# P06_BoosterPack_Headers.net
KiCad netlist of a schematic drawn in Altium Designer
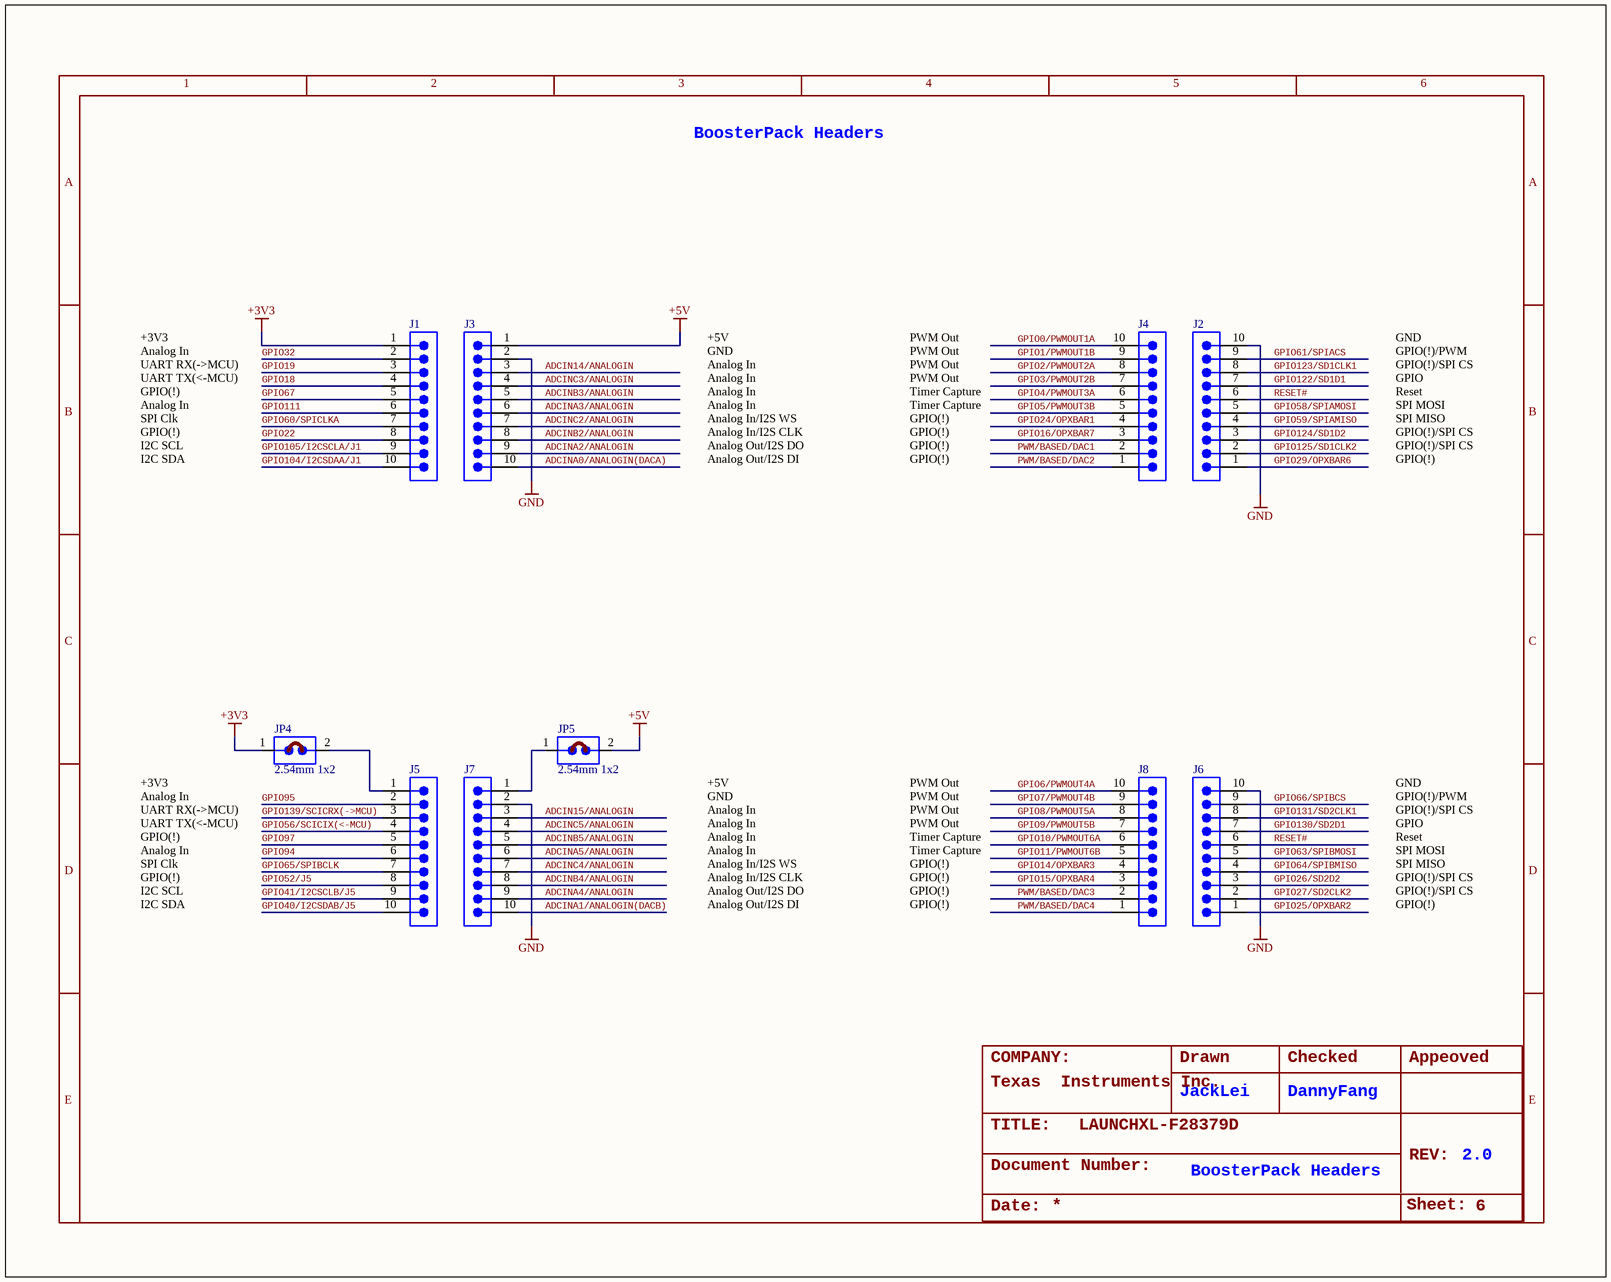
[diagram p0: P06_BoosterPack Headers.SchDoc]

(export (version "E")
  (design (tool "Eeschema 10.0.6"))
  (components
    (comp (ref "J1")
      (value "FH2543-10GT10")
      (footprint "SOKV2W64P254_1X10_2590X250X850P")
      (description "Connector,Pin Socket,Straight,Female,1x10Pin,2.54MM pitch,8.5,3.2,Gold Flash 1u,black,DIP")
      (fields (field (name "MANUFACTURER") "MTCONN"))
      (libsource (lib "") (part "SIP10_1"))
    )
    (comp (ref "J2")
      (value "FH2543-10GT10")
      (footprint "SOKV2W64P254_1X10_2590X250X850P")
      (description "Connector,Pin Socket,Straight,Female,1x10Pin,2.54MM pitch,8.5,3.2,Gold Flash 1u,black,DIP")
      (fields (field (name "MANUFACTURER") "MTCONN"))
      (libsource (lib "") (part "SIP10_3"))
    )
    (comp (ref "J3")
      (value "FH2543-10GT10")
      (footprint "SOKV2W64P254_1X10_2590X250X850P")
      (description "Connector,Pin Socket,Straight,Female,1x10Pin,2.54MM pitch,8.5,3.2,Gold Flash 1u,black,DIP")
      (fields (field (name "MANUFACTURER") "MTCONN"))
      (libsource (lib "Embest") (part "SIP10"))
    )
    (comp (ref "J4")
      (value "FH2543-10GT10")
      (footprint "SOKV2W64P254_1X10_2590X250X850P")
      (description "Connector,Pin Socket,Straight,Female,1x10Pin,2.54MM pitch,8.5,3.2,Gold Flash 1u,black,DIP")
      (fields (field (name "MANUFACTURER") "MTCONN"))
      (libsource (lib "") (part "SIP10_2"))
    )
    (comp (ref "J5")
      (value "FH2543-10GT10")
      (footprint "SOKV2W64P254_1X10_2590X250X850P")
      (description "Connector,Pin Socket,Straight,Female,1x10Pin,2.54MM pitch,8.5,3.2,Gold Flash 1u,black,DIP")
      (fields (field (name "MANUFACTURER") "MTCONN"))
      (libsource (lib "") (part "SIP10_1"))
    )
    (comp (ref "J6")
      (value "FH2543-10GT10")
      (footprint "SOKV2W64P254_1X10_2590X250X850P")
      (description "Connector,Pin Socket,Straight,Female,1x10Pin,2.54MM pitch,8.5,3.2,Gold Flash 1u,black,DIP")
      (fields (field (name "MANUFACTURER") "MTCONN"))
      (libsource (lib "") (part "SIP10_3"))
    )
    (comp (ref "J7")
      (value "FH2543-10GT10")
      (footprint "SOKV2W64P254_1X10_2590X250X850P")
      (description "Connector,Pin Socket,Straight,Female,1x10Pin,2.54MM pitch,8.5,3.2,Gold Flash 1u,black,DIP")
      (fields (field (name "MANUFACTURER") "MTCONN"))
      (libsource (lib "Embest") (part "SIP10"))
    )
    (comp (ref "J8")
      (value "FH2543-10GT10")
      (footprint "SOKV2W64P254_1X10_2590X250X850P")
      (description "Connector,Pin Socket,Straight,Female,1x10Pin,2.54MM pitch,8.5,3.2,Gold Flash 1u,black,DIP")
      (fields (field (name "MANUFACTURER") "MTCONN"))
      (libsource (lib "") (part "SIP10_2"))
    )
    (comp (ref "JP4")
      (value "2.54mm 1x2")
      (footprint "HDRV2W64P254_1X2_508X250X850P")
      (fields
        (field (name "MANUFACTURER") "CHIN-BAN")
        (field (name "MANUFACTURER PART NUMBER") "P6E02A-602530-B1")
      )
      (libsource (lib "Embest") (part "SIP2"))
    )
    (comp (ref "JP5")
      (value "2.54mm 1x2")
      (footprint "HDRV2W64P254_1X2_508X250X850P")
      (fields
        (field (name "MANUFACTURER") "CHIN-BAN")
        (field (name "MANUFACTURER PART NUMBER") "P6E02A-602530-B1")
      )
      (libsource (lib "Embest") (part "SIP2"))
    )
    (comp (ref "U$12")
      (value "ROY_JUMPER")
      (footprint "ROY_JUMPER")
      (libsource (lib "roy") (part "ROY_JUMPER"))
    )
    (comp (ref "U$13")
      (value "ROY_JUMPER")
      (footprint "ROY_JUMPER")
      (libsource (lib "roy") (part "ROY_JUMPER"))
    )
  )
  (nets
    (net (code "1") (name "+3V3") (class "Default")
      (node (ref "J1") (pin "1") (pinfunction "1_1") (pintype "passive"))
      (node (ref "JP4") (pin "1") (pinfunction "1_1") (pintype "passive"))
    )
    (net (code "2") (name "+5V") (class "Default")
      (node (ref "J3") (pin "1") (pinfunction "1_1") (pintype "passive"))
      (node (ref "JP5") (pin "2") (pinfunction "2_2") (pintype "passive"))
    )
    (net (code "3") (name "/ADCIN14{slash}ANALOGIN") (class "Default")
      (node (ref "J3") (pin "3") (pinfunction "3_3") (pintype "passive"))
    )
    (net (code "4") (name "/ADCIN15{slash}ANALOGIN") (class "Default")
      (node (ref "J7") (pin "3") (pinfunction "3_3") (pintype "passive"))
    )
    (net (code "5") (name "/ADCINA0{slash}ANALOGIN(DACA)") (class "Default")
      (node (ref "J3") (pin "10") (pinfunction "10_10") (pintype "passive"))
    )
    (net (code "6") (name "/ADCINA1{slash}ANALOGIN(DACB)") (class "Default")
      (node (ref "J7") (pin "10") (pinfunction "10_10") (pintype "passive"))
    )
    (net (code "7") (name "/ADCINA2{slash}ANALOGIN") (class "Default")
      (node (ref "J3") (pin "9") (pinfunction "9_9") (pintype "passive"))
    )
    (net (code "8") (name "/ADCINA3{slash}ANALOGIN") (class "Default")
      (node (ref "J3") (pin "6") (pinfunction "6_6") (pintype "passive"))
    )
    (net (code "9") (name "/ADCINA4{slash}ANALOGIN") (class "Default")
      (node (ref "J7") (pin "9") (pinfunction "9_9") (pintype "passive"))
    )
    (net (code "10") (name "/ADCINA5{slash}ANALOGIN") (class "Default")
      (node (ref "J7") (pin "6") (pinfunction "6_6") (pintype "passive"))
    )
    (net (code "11") (name "/ADCINB2{slash}ANALOGIN") (class "Default")
      (node (ref "J3") (pin "8") (pinfunction "8_8") (pintype "passive"))
    )
    (net (code "12") (name "/ADCINB3{slash}ANALOGIN") (class "Default")
      (node (ref "J3") (pin "5") (pinfunction "5_5") (pintype "passive"))
    )
    (net (code "13") (name "/ADCINB4{slash}ANALOGIN") (class "Default")
      (node (ref "J7") (pin "8") (pinfunction "8_8") (pintype "passive"))
    )
    (net (code "14") (name "/ADCINB5{slash}ANALOGIN") (class "Default")
      (node (ref "J7") (pin "5") (pinfunction "5_5") (pintype "passive"))
    )
    (net (code "15") (name "/ADCINC2{slash}ANALOGIN") (class "Default")
      (node (ref "J3") (pin "7") (pinfunction "7_7") (pintype "passive"))
    )
    (net (code "16") (name "/ADCINC3{slash}ANALOGIN") (class "Default")
      (node (ref "J3") (pin "4") (pinfunction "4_4") (pintype "passive"))
    )
    (net (code "17") (name "/ADCINC4{slash}ANALOGIN") (class "Default")
      (node (ref "J7") (pin "7") (pinfunction "7_7") (pintype "passive"))
    )
    (net (code "18") (name "/ADCINC5{slash}ANALOGIN") (class "Default")
      (node (ref "J7") (pin "4") (pinfunction "4_4") (pintype "passive"))
    )
    (net (code "19") (name "/GPIO0{slash}PWMOUT1A") (class "Default")
      (node (ref "J4") (pin "10") (pinfunction "10_10") (pintype "passive"))
    )
    (net (code "20") (name "/GPIO1{slash}PWMOUT1B") (class "Default")
      (node (ref "J4") (pin "9") (pinfunction "9_9") (pintype "passive"))
    )
    (net (code "21") (name "/GPIO2{slash}PWMOUT2A") (class "Default")
      (node (ref "J4") (pin "8") (pinfunction "8_8") (pintype "passive"))
    )
    (net (code "22") (name "/GPIO3{slash}PWMOUT2B") (class "Default")
      (node (ref "J4") (pin "7") (pinfunction "7_7") (pintype "passive"))
    )
    (net (code "23") (name "/GPIO4{slash}PWMOUT3A") (class "Default")
      (node (ref "J4") (pin "6") (pinfunction "6_6") (pintype "passive"))
    )
    (net (code "24") (name "/GPIO5{slash}PWMOUT3B") (class "Default")
      (node (ref "J4") (pin "5") (pinfunction "5_5") (pintype "passive"))
    )
    (net (code "25") (name "/GPIO6{slash}PWMOUT4A") (class "Default")
      (node (ref "J8") (pin "10") (pinfunction "10_10") (pintype "passive"))
    )
    (net (code "26") (name "/GPIO7{slash}PWMOUT4B") (class "Default")
      (node (ref "J8") (pin "9") (pinfunction "9_9") (pintype "passive"))
    )
    (net (code "27") (name "/GPIO8{slash}PWMOUT5A") (class "Default")
      (node (ref "J8") (pin "8") (pinfunction "8_8") (pintype "passive"))
    )
    (net (code "28") (name "/GPIO9{slash}PWMOUT5B") (class "Default")
      (node (ref "J8") (pin "7") (pinfunction "7_7") (pintype "passive"))
    )
    (net (code "29") (name "/GPIO10{slash}PWMOUT6A") (class "Default")
      (node (ref "J8") (pin "6") (pinfunction "6_6") (pintype "passive"))
    )
    (net (code "30") (name "/GPIO11{slash}PWMOUT6B") (class "Default")
      (node (ref "J8") (pin "5") (pinfunction "5_5") (pintype "passive"))
    )
    (net (code "31") (name "/GPIO14{slash}OPXBAR3") (class "Default")
      (node (ref "J8") (pin "4") (pinfunction "4_4") (pintype "passive"))
    )
    (net (code "32") (name "/GPIO15{slash}OPXBAR4") (class "Default")
      (node (ref "J8") (pin "3") (pinfunction "3_3") (pintype "passive"))
    )
    (net (code "33") (name "/GPIO16{slash}OPXBAR7") (class "Default")
      (node (ref "J4") (pin "3") (pinfunction "3_3") (pintype "passive"))
    )
    (net (code "34") (name "/GPIO18") (class "Default")
      (node (ref "J1") (pin "4") (pinfunction "4_4") (pintype "passive"))
    )
    (net (code "35") (name "/GPIO19") (class "Default")
      (node (ref "J1") (pin "3") (pinfunction "3_3") (pintype "passive"))
    )
    (net (code "36") (name "/GPIO22") (class "Default")
      (node (ref "J1") (pin "8") (pinfunction "8_8") (pintype "passive"))
    )
    (net (code "37") (name "/GPIO24{slash}OPXBAR1") (class "Default")
      (node (ref "J4") (pin "4") (pinfunction "4_4") (pintype "passive"))
    )
    (net (code "38") (name "/GPIO25{slash}OPXBAR2") (class "Default")
      (node (ref "J6") (pin "1") (pinfunction "1_1") (pintype "passive"))
    )
    (net (code "39") (name "/GPIO26{slash}SD2D2") (class "Default")
      (node (ref "J6") (pin "3") (pinfunction "3_3") (pintype "passive"))
    )
    (net (code "40") (name "/GPIO27{slash}SD2CLK2") (class "Default")
      (node (ref "J6") (pin "2") (pinfunction "2_2") (pintype "passive"))
    )
    (net (code "41") (name "/GPIO29{slash}OPXBAR6") (class "Default")
      (node (ref "J2") (pin "1") (pinfunction "1_1") (pintype "passive"))
    )
    (net (code "42") (name "/GPIO32") (class "Default")
      (node (ref "J1") (pin "2") (pinfunction "2_2") (pintype "passive"))
    )
    (net (code "43") (name "/GPIO40{slash}I2CSDAB{slash}J5") (class "Default")
      (node (ref "J5") (pin "10") (pinfunction "10_10") (pintype "passive"))
    )
    (net (code "44") (name "/GPIO41{slash}I2CSCLB{slash}J5") (class "Default")
      (node (ref "J5") (pin "9") (pinfunction "9_9") (pintype "passive"))
    )
    (net (code "45") (name "/GPIO52{slash}J5") (class "Default")
      (node (ref "J5") (pin "8") (pinfunction "8_8") (pintype "passive"))
    )
    (net (code "46") (name "/GPIO56{slash}SCICIX(<-MCU)") (class "Default")
      (node (ref "J5") (pin "4") (pinfunction "4_4") (pintype "passive"))
    )
    (net (code "47") (name "/GPIO58{slash}SPIAMOSI") (class "Default")
      (node (ref "J2") (pin "5") (pinfunction "5_5") (pintype "passive"))
    )
    (net (code "48") (name "/GPIO59{slash}SPIAMISO") (class "Default")
      (node (ref "J2") (pin "4") (pinfunction "4_4") (pintype "passive"))
    )
    (net (code "49") (name "/GPIO60{slash}SPICLKA") (class "Default")
      (node (ref "J1") (pin "7") (pinfunction "7_7") (pintype "passive"))
    )
    (net (code "50") (name "/GPIO61{slash}SPIACS") (class "Default")
      (node (ref "J2") (pin "9") (pinfunction "9_9") (pintype "passive"))
    )
    (net (code "51") (name "/GPIO63{slash}SPIBMOSI") (class "Default")
      (node (ref "J6") (pin "5") (pinfunction "5_5") (pintype "passive"))
    )
    (net (code "52") (name "/GPIO64{slash}SPIBMISO") (class "Default")
      (node (ref "J6") (pin "4") (pinfunction "4_4") (pintype "passive"))
    )
    (net (code "53") (name "/GPIO65{slash}SPIBCLK") (class "Default")
      (node (ref "J5") (pin "7") (pinfunction "7_7") (pintype "passive"))
    )
    (net (code "54") (name "/GPIO66{slash}SPIBCS") (class "Default")
      (node (ref "J6") (pin "9") (pinfunction "9_9") (pintype "passive"))
    )
    (net (code "55") (name "/GPIO67") (class "Default")
      (node (ref "J1") (pin "5") (pinfunction "5_5") (pintype "passive"))
    )
    (net (code "56") (name "/GPIO94") (class "Default")
      (node (ref "J5") (pin "6") (pinfunction "6_6") (pintype "passive"))
    )
    (net (code "57") (name "/GPIO95") (class "Default")
      (node (ref "J5") (pin "2") (pinfunction "2_2") (pintype "passive"))
    )
    (net (code "58") (name "/GPIO97") (class "Default")
      (node (ref "J5") (pin "5") (pinfunction "5_5") (pintype "passive"))
    )
    (net (code "59") (name "/GPIO104{slash}I2CSDAA{slash}J1") (class "Default")
      (node (ref "J1") (pin "10") (pinfunction "10_10") (pintype "passive"))
    )
    (net (code "60") (name "/GPIO105{slash}I2CSCLA{slash}J1") (class "Default")
      (node (ref "J1") (pin "9") (pinfunction "9_9") (pintype "passive"))
    )
    (net (code "61") (name "/GPIO111") (class "Default")
      (node (ref "J1") (pin "6") (pinfunction "6_6") (pintype "passive"))
    )
    (net (code "62") (name "/GPIO122{slash}SD1D1") (class "Default")
      (node (ref "J2") (pin "7") (pinfunction "7_7") (pintype "passive"))
    )
    (net (code "63") (name "/GPIO123{slash}SD1CLK1") (class "Default")
      (node (ref "J2") (pin "8") (pinfunction "8_8") (pintype "passive"))
    )
    (net (code "64") (name "/GPIO124{slash}SD1D2") (class "Default")
      (node (ref "J2") (pin "3") (pinfunction "3_3") (pintype "passive"))
    )
    (net (code "65") (name "/GPIO125{slash}SD1CLK2") (class "Default")
      (node (ref "J2") (pin "2") (pinfunction "2_2") (pintype "passive"))
    )
    (net (code "66") (name "/GPIO130{slash}SD2D1") (class "Default")
      (node (ref "J6") (pin "7") (pinfunction "7_7") (pintype "passive"))
    )
    (net (code "67") (name "/GPIO131{slash}SD2CLK1") (class "Default")
      (node (ref "J6") (pin "8") (pinfunction "8_8") (pintype "passive"))
    )
    (net (code "68") (name "/GPIO139{slash}SCICRX(->MCU)") (class "Default")
      (node (ref "J5") (pin "3") (pinfunction "3_3") (pintype "passive"))
    )
    (net (code "69") (name "/PWM{slash}BASED{slash}DAC1") (class "Default")
      (node (ref "J4") (pin "2") (pinfunction "2_2") (pintype "passive"))
    )
    (net (code "70") (name "/PWM{slash}BASED{slash}DAC2") (class "Default")
      (node (ref "J4") (pin "1") (pinfunction "1_1") (pintype "passive"))
    )
    (net (code "71") (name "/PWM{slash}BASED{slash}DAC3") (class "Default")
      (node (ref "J8") (pin "2") (pinfunction "2_2") (pintype "passive"))
    )
    (net (code "72") (name "/PWM{slash}BASED{slash}DAC4") (class "Default")
      (node (ref "J8") (pin "1") (pinfunction "1_1") (pintype "passive"))
    )
    (net (code "73") (name "/RESET#") (class "Default")
      (node (ref "J2") (pin "6") (pinfunction "6_6") (pintype "passive"))
      (node (ref "J6") (pin "6") (pinfunction "6_6") (pintype "passive"))
    )
    (net (code "74") (name "GND") (class "Default")
      (node (ref "J2") (pin "10") (pinfunction "10_10") (pintype "passive"))
      (node (ref "J3") (pin "2") (pinfunction "2_2") (pintype "passive"))
      (node (ref "J6") (pin "10") (pinfunction "10_10") (pintype "passive"))
      (node (ref "J7") (pin "2") (pinfunction "2_2") (pintype "passive"))
    )
    (net (code "75") (name "Net-(J5-Pad1)") (class "Default")
      (node (ref "J5") (pin "1") (pinfunction "1_1") (pintype "passive"))
      (node (ref "JP4") (pin "2") (pinfunction "2_2") (pintype "passive"))
    )
    (net (code "76") (name "Net-(J7-Pad1)") (class "Default")
      (node (ref "J7") (pin "1") (pinfunction "1_1") (pintype "passive"))
      (node (ref "JP5") (pin "1") (pinfunction "1_1") (pintype "passive"))
    )
  )
)
